# Shield_Kazi.net
KiCad netlist of a schematic drawn in EAGLE
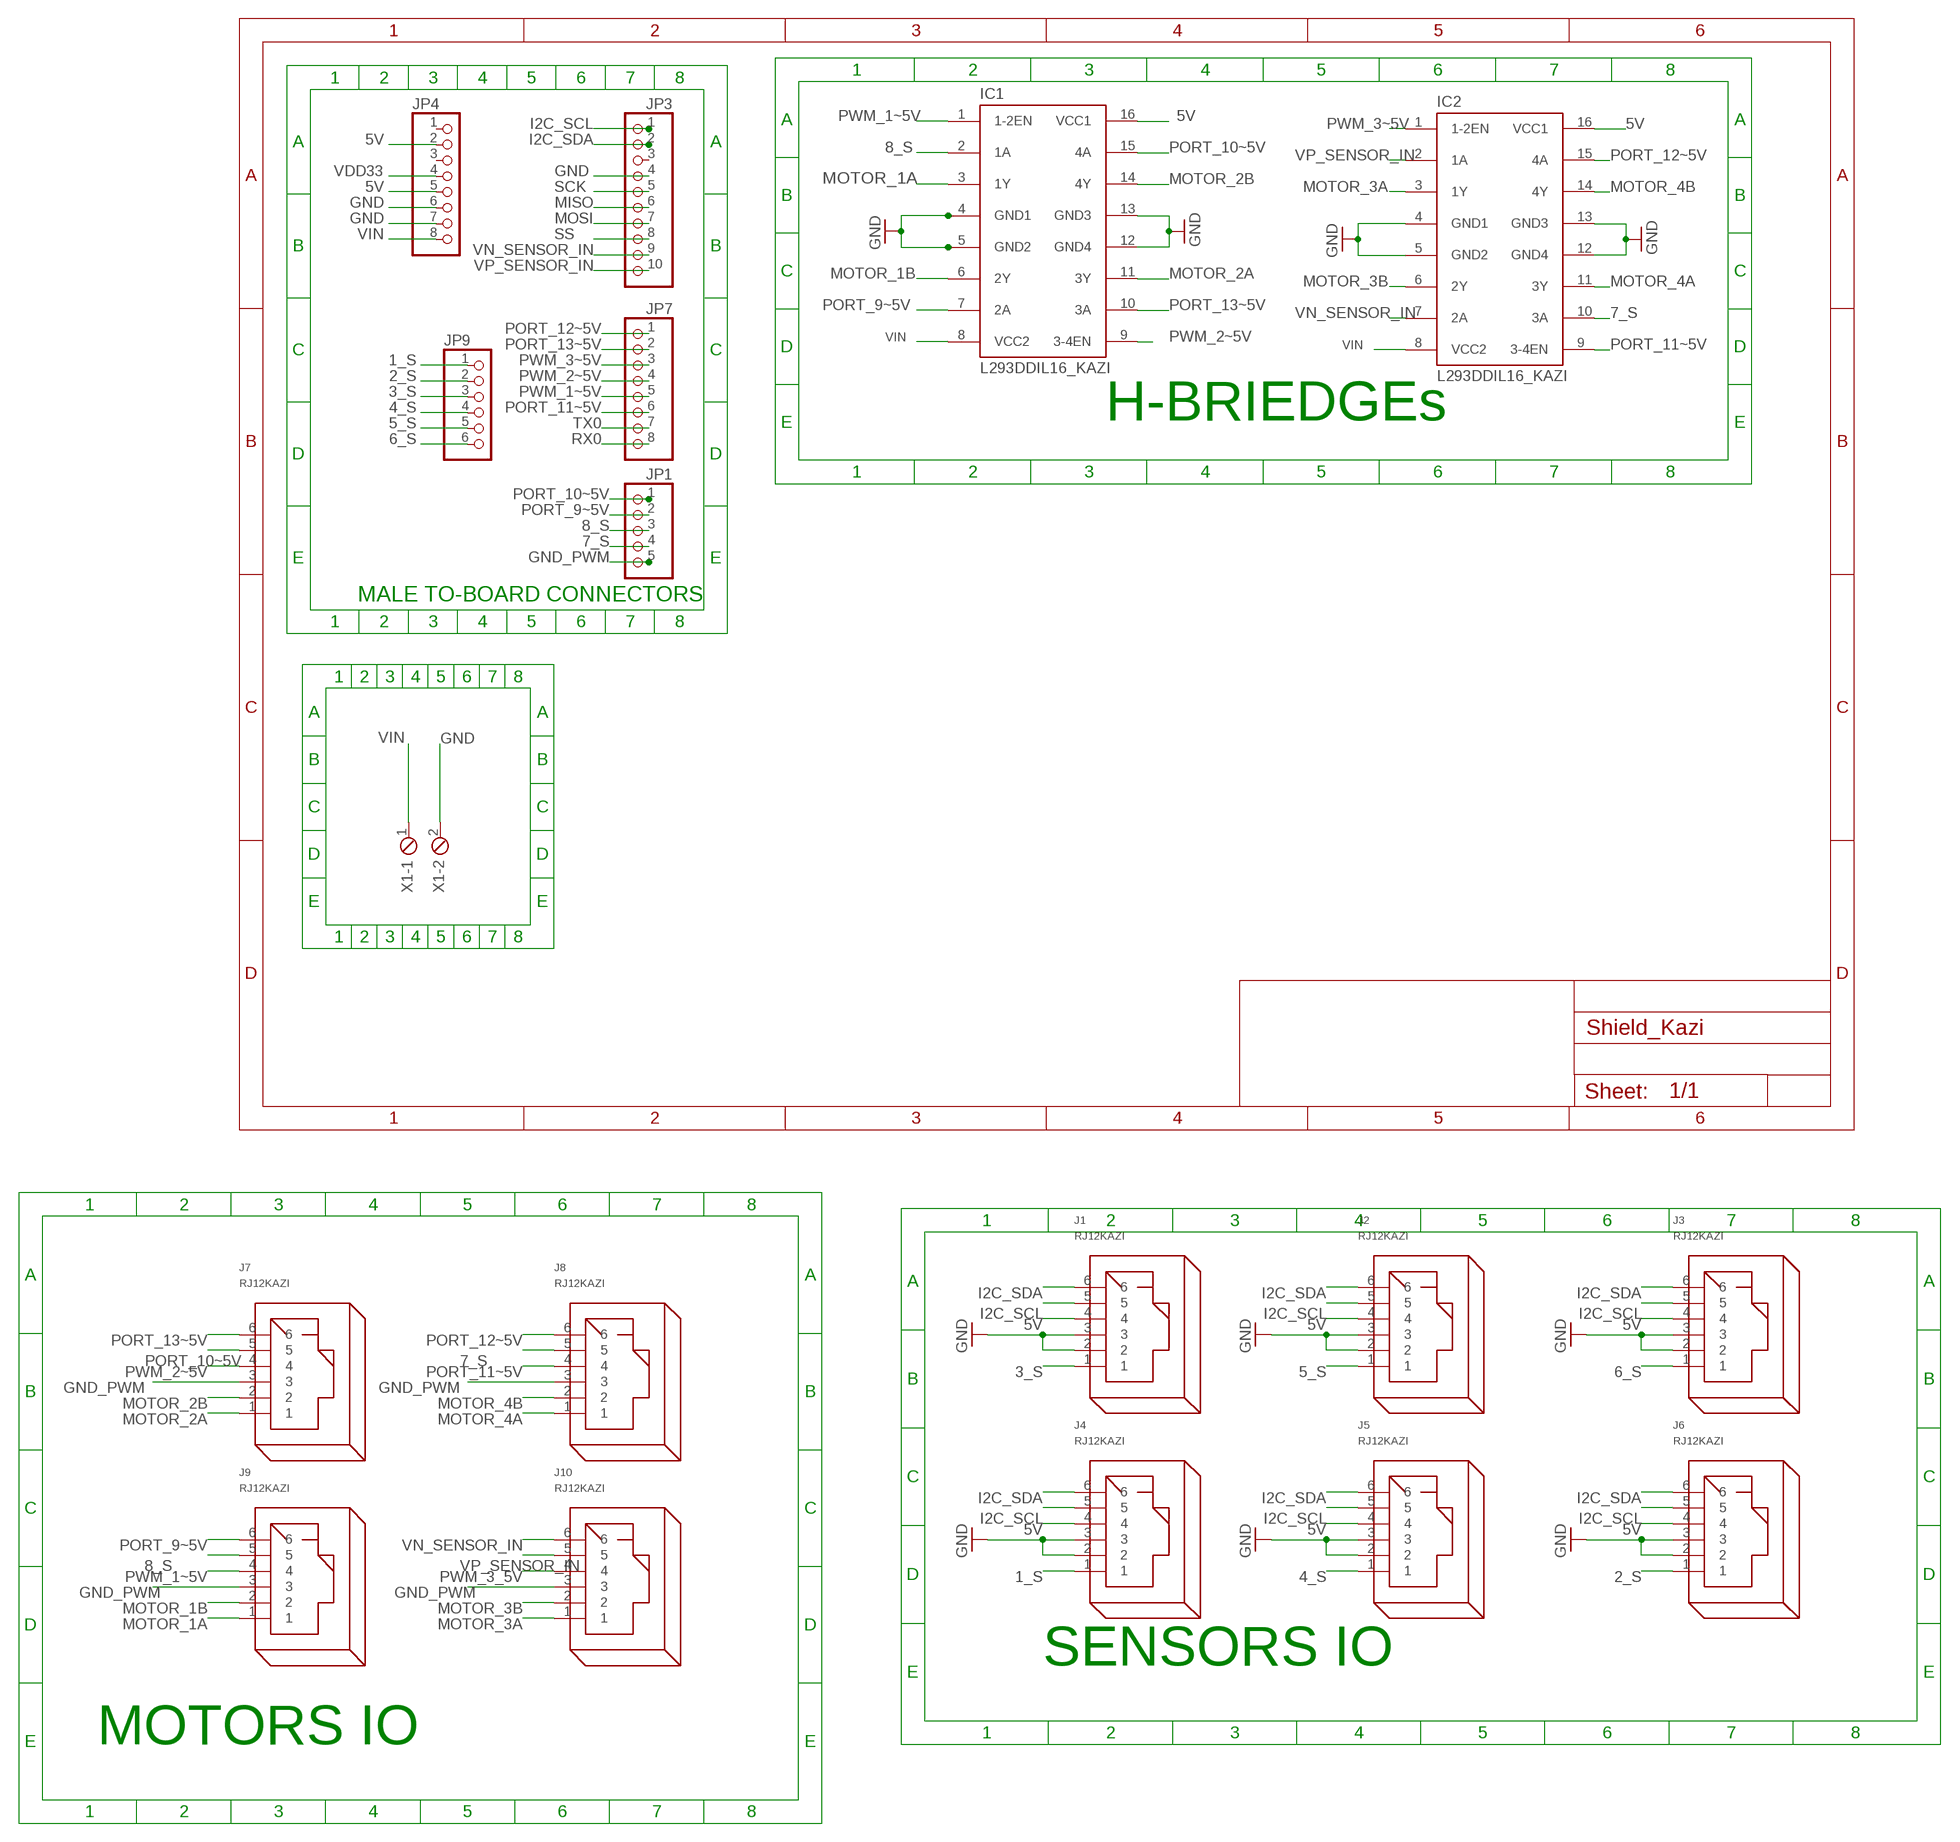
[diagram p0: schematic, sheet 1]

(export (version "E")
  (design (tool "Eeschema 10.0.6"))
  (components
    (comp (ref "IC1")
      (value "L293DDIL16_KAZI")
      (footprint "eagle-import:DIL16_KAZI")
      (libsource (lib "eagle-import") (part "L293DDIL16_KAZI"))
    )
    (comp (ref "IC2")
      (value "L293DDIL16_KAZI")
      (footprint "eagle-import:DIL16_KAZI")
      (libsource (lib "eagle-import") (part "L293DDIL16_KAZI"))
    )
    (comp (ref "J1")
      (value "RJ12KAZI")
      (footprint "eagle-import:RJ12_KAZI")
      (libsource (lib "eagle-import") (part "RJ12KAZI"))
    )
    (comp (ref "J2")
      (value "RJ12KAZI")
      (footprint "eagle-import:RJ12_KAZI")
      (libsource (lib "eagle-import") (part "RJ12KAZI"))
    )
    (comp (ref "J3")
      (value "RJ12KAZI")
      (footprint "eagle-import:RJ12_KAZI")
      (libsource (lib "eagle-import") (part "RJ12KAZI"))
    )
    (comp (ref "J4")
      (value "RJ12KAZI")
      (footprint "eagle-import:RJ12_KAZI")
      (libsource (lib "eagle-import") (part "RJ12KAZI"))
    )
    (comp (ref "J5")
      (value "RJ12KAZI")
      (footprint "eagle-import:RJ12_KAZI")
      (libsource (lib "eagle-import") (part "RJ12KAZI"))
    )
    (comp (ref "J6")
      (value "RJ12KAZI")
      (footprint "eagle-import:RJ12_KAZI")
      (libsource (lib "eagle-import") (part "RJ12KAZI"))
    )
    (comp (ref "J7")
      (value "RJ12KAZI")
      (footprint "eagle-import:RJ12_KAZI")
      (libsource (lib "eagle-import") (part "RJ12KAZI"))
    )
    (comp (ref "J8")
      (value "RJ12KAZI")
      (footprint "eagle-import:RJ12_KAZI")
      (libsource (lib "eagle-import") (part "RJ12KAZI"))
    )
    (comp (ref "J9")
      (value "RJ12KAZI")
      (footprint "eagle-import:RJ12_KAZI")
      (libsource (lib "eagle-import") (part "RJ12KAZI"))
    )
    (comp (ref "J10")
      (value "RJ12KAZI")
      (footprint "eagle-import:RJ12_KAZI")
      (libsource (lib "eagle-import") (part "RJ12KAZI"))
    )
    (comp (ref "JP1")
      (value "PINHD-1X5_2.54-SMD")
      (footprint "eagle-import:1X05SMD")
      (libsource (lib "eagle-import") (part "PINHD-1X5_2.54-SMD"))
    )
    (comp (ref "JP3")
      (value "PINHD-1X10_2.54-SMD")
      (footprint "eagle-import:1X10SMD")
      (libsource (lib "eagle-import") (part "PINHD-1X10_2.54-SMD"))
    )
    (comp (ref "JP4")
      (value "PINHD-1X8_2.54-SMD")
      (footprint "eagle-import:1X08SMD")
      (libsource (lib "eagle-import") (part "PINHD-1X8_2.54-SMD"))
    )
    (comp (ref "JP7")
      (value "PINHD-1X8_2.54-SMD")
      (footprint "eagle-import:1X08SMD")
      (libsource (lib "eagle-import") (part "PINHD-1X8_2.54-SMD"))
    )
    (comp (ref "JP9")
      (value "PINHD-1X6_2.54-SMD")
      (footprint "eagle-import:1X06SMD")
      (libsource (lib "eagle-import") (part "PINHD-1X6_2.54-SMD"))
    )
    (comp (ref "X1")
      (value "MPT21.3")
      (footprint "eagle-import:2POL254_1.3")
      (libsource (lib "eagle-import") (part "MPT21.3"))
    )
  )
  (nets
    (net (code "1") (name "/1_S") (class "Default")
      (node (ref "J4") (pin "1") (pinfunction "1_1") (pintype "bidirectional"))
      (node (ref "JP9") (pin "1") (pinfunction "1_1") (pintype "passive"))
    )
    (net (code "2") (name "/2_S") (class "Default")
      (node (ref "J6") (pin "1") (pinfunction "1_1") (pintype "bidirectional"))
      (node (ref "JP9") (pin "2") (pinfunction "2_2") (pintype "passive"))
    )
    (net (code "3") (name "/3_S") (class "Default")
      (node (ref "J1") (pin "1") (pinfunction "1_1") (pintype "bidirectional"))
      (node (ref "JP9") (pin "3") (pinfunction "3_3") (pintype "passive"))
    )
    (net (code "4") (name "/4_S") (class "Default")
      (node (ref "J5") (pin "1") (pinfunction "1_1") (pintype "bidirectional"))
      (node (ref "JP9") (pin "4") (pinfunction "4_4") (pintype "passive"))
    )
    (net (code "5") (name "/5V") (class "Default")
      (node (ref "IC1") (pin "16") (pinfunction "VCC1_16") (pintype "power_in"))
      (node (ref "IC2") (pin "16") (pinfunction "VCC1_16") (pintype "power_in"))
      (node (ref "J1") (pin "4") (pinfunction "4_4") (pintype "bidirectional"))
      (node (ref "J2") (pin "4") (pinfunction "4_4") (pintype "bidirectional"))
      (node (ref "J3") (pin "4") (pinfunction "4_4") (pintype "bidirectional"))
      (node (ref "J4") (pin "4") (pinfunction "4_4") (pintype "bidirectional"))
      (node (ref "J5") (pin "4") (pinfunction "4_4") (pintype "bidirectional"))
      (node (ref "J6") (pin "4") (pinfunction "4_4") (pintype "bidirectional"))
      (node (ref "JP4") (pin "2") (pinfunction "2_2") (pintype "passive"))
      (node (ref "JP4") (pin "5") (pinfunction "5_5") (pintype "passive"))
    )
    (net (code "6") (name "/5_S") (class "Default")
      (node (ref "J2") (pin "1") (pinfunction "1_1") (pintype "bidirectional"))
      (node (ref "JP9") (pin "5") (pinfunction "5_5") (pintype "passive"))
    )
    (net (code "7") (name "/6_S") (class "Default")
      (node (ref "J3") (pin "1") (pinfunction "1_1") (pintype "bidirectional"))
      (node (ref "JP9") (pin "6") (pinfunction "6_6") (pintype "passive"))
    )
    (net (code "8") (name "/7_S") (class "Default")
      (node (ref "IC2") (pin "10") (pinfunction "3A_10") (pintype "input"))
      (node (ref "J8") (pin "5") (pinfunction "5_5") (pintype "bidirectional"))
      (node (ref "JP1") (pin "4") (pinfunction "4_4") (pintype "passive"))
    )
    (net (code "9") (name "/8_S") (class "Default")
      (node (ref "IC1") (pin "2") (pinfunction "1A_2") (pintype "input"))
      (node (ref "J9") (pin "5") (pinfunction "5_5") (pintype "bidirectional"))
      (node (ref "JP1") (pin "3") (pinfunction "3_3") (pintype "passive"))
    )
    (net (code "10") (name "/GND_PWM") (class "Default")
      (node (ref "J10") (pin "3") (pinfunction "3_3") (pintype "bidirectional"))
      (node (ref "J7") (pin "3") (pinfunction "3_3") (pintype "bidirectional"))
      (node (ref "J8") (pin "3") (pinfunction "3_3") (pintype "bidirectional"))
      (node (ref "J9") (pin "3") (pinfunction "3_3") (pintype "bidirectional"))
      (node (ref "JP1") (pin "5") (pinfunction "5_5") (pintype "passive"))
    )
    (net (code "11") (name "/I2C_SCL") (class "Default")
      (node (ref "J1") (pin "5") (pinfunction "5_5") (pintype "bidirectional"))
      (node (ref "J2") (pin "5") (pinfunction "5_5") (pintype "bidirectional"))
      (node (ref "J3") (pin "5") (pinfunction "5_5") (pintype "bidirectional"))
      (node (ref "J4") (pin "5") (pinfunction "5_5") (pintype "bidirectional"))
      (node (ref "J5") (pin "5") (pinfunction "5_5") (pintype "bidirectional"))
      (node (ref "J6") (pin "5") (pinfunction "5_5") (pintype "bidirectional"))
      (node (ref "JP3") (pin "1") (pinfunction "1_1") (pintype "passive"))
    )
    (net (code "12") (name "/I2C_SDA") (class "Default")
      (node (ref "J1") (pin "6") (pinfunction "6_6") (pintype "bidirectional"))
      (node (ref "J2") (pin "6") (pinfunction "6_6") (pintype "bidirectional"))
      (node (ref "J3") (pin "6") (pinfunction "6_6") (pintype "bidirectional"))
      (node (ref "J4") (pin "6") (pinfunction "6_6") (pintype "bidirectional"))
      (node (ref "J5") (pin "6") (pinfunction "6_6") (pintype "bidirectional"))
      (node (ref "J6") (pin "6") (pinfunction "6_6") (pintype "bidirectional"))
      (node (ref "JP3") (pin "2") (pinfunction "2_2") (pintype "passive"))
    )
    (net (code "13") (name "/MISO") (class "Default")
      (node (ref "JP3") (pin "6") (pinfunction "6_6") (pintype "passive"))
    )
    (net (code "14") (name "/MOSI") (class "Default")
      (node (ref "JP3") (pin "7") (pinfunction "7_7") (pintype "passive"))
    )
    (net (code "15") (name "/MOTOR_1A") (class "Default")
      (node (ref "IC1") (pin "3") (pinfunction "1Y_3") (pintype "output"))
      (node (ref "J9") (pin "1") (pinfunction "1_1") (pintype "bidirectional"))
    )
    (net (code "16") (name "/MOTOR_1B") (class "Default")
      (node (ref "IC1") (pin "6") (pinfunction "2Y_6") (pintype "output"))
      (node (ref "J9") (pin "2") (pinfunction "2_2") (pintype "bidirectional"))
    )
    (net (code "17") (name "/MOTOR_2A") (class "Default")
      (node (ref "IC1") (pin "11") (pinfunction "3Y_11") (pintype "output"))
      (node (ref "J7") (pin "1") (pinfunction "1_1") (pintype "bidirectional"))
    )
    (net (code "18") (name "/MOTOR_2B") (class "Default")
      (node (ref "IC1") (pin "14") (pinfunction "4Y_14") (pintype "output"))
      (node (ref "J7") (pin "2") (pinfunction "2_2") (pintype "bidirectional"))
    )
    (net (code "19") (name "/MOTOR_3A") (class "Default")
      (node (ref "IC2") (pin "3") (pinfunction "1Y_3") (pintype "output"))
      (node (ref "J10") (pin "1") (pinfunction "1_1") (pintype "bidirectional"))
    )
    (net (code "20") (name "/MOTOR_3B") (class "Default")
      (node (ref "IC2") (pin "6") (pinfunction "2Y_6") (pintype "output"))
      (node (ref "J10") (pin "2") (pinfunction "2_2") (pintype "bidirectional"))
    )
    (net (code "21") (name "/MOTOR_4A") (class "Default")
      (node (ref "IC2") (pin "11") (pinfunction "3Y_11") (pintype "output"))
      (node (ref "J8") (pin "1") (pinfunction "1_1") (pintype "bidirectional"))
    )
    (net (code "22") (name "/MOTOR_4B") (class "Default")
      (node (ref "IC2") (pin "14") (pinfunction "4Y_14") (pintype "output"))
      (node (ref "J8") (pin "2") (pinfunction "2_2") (pintype "bidirectional"))
    )
    (net (code "23") (name "/PORT_9~{5V}") (class "Default")
      (node (ref "IC1") (pin "7") (pinfunction "2A_7") (pintype "input"))
      (node (ref "J9") (pin "6") (pinfunction "6_6") (pintype "bidirectional"))
      (node (ref "JP1") (pin "2") (pinfunction "2_2") (pintype "passive"))
    )
    (net (code "24") (name "/PORT_10~{5V}") (class "Default")
      (node (ref "IC1") (pin "15") (pinfunction "4A_15") (pintype "input"))
      (node (ref "J7") (pin "5") (pinfunction "5_5") (pintype "bidirectional"))
      (node (ref "JP1") (pin "1") (pinfunction "1_1") (pintype "passive"))
    )
    (net (code "25") (name "/PORT_11~{5V}") (class "Default")
      (node (ref "IC2") (pin "9") (pinfunction "3-4EN_9") (pintype "input"))
      (node (ref "J8") (pin "4") (pinfunction "4_4") (pintype "bidirectional"))
      (node (ref "JP7") (pin "6") (pinfunction "6_6") (pintype "passive"))
    )
    (net (code "26") (name "/PORT_12~{5V}") (class "Default")
      (node (ref "IC2") (pin "15") (pinfunction "4A_15") (pintype "input"))
      (node (ref "J8") (pin "6") (pinfunction "6_6") (pintype "bidirectional"))
      (node (ref "JP7") (pin "1") (pinfunction "1_1") (pintype "passive"))
    )
    (net (code "27") (name "/PORT_13~{5V}") (class "Default")
      (node (ref "IC1") (pin "10") (pinfunction "3A_10") (pintype "input"))
      (node (ref "J7") (pin "6") (pinfunction "6_6") (pintype "bidirectional"))
      (node (ref "JP7") (pin "2") (pinfunction "2_2") (pintype "passive"))
    )
    (net (code "28") (name "/PWM_1~{5V}") (class "Default")
      (node (ref "IC1") (pin "1") (pinfunction "1-2EN_1") (pintype "input"))
      (node (ref "J9") (pin "4") (pinfunction "4_4") (pintype "bidirectional"))
      (node (ref "JP7") (pin "5") (pinfunction "5_5") (pintype "passive"))
    )
    (net (code "29") (name "/PWM_2~{5V}") (class "Default")
      (node (ref "IC1") (pin "9") (pinfunction "3-4EN_9") (pintype "input"))
      (node (ref "J7") (pin "4") (pinfunction "4_4") (pintype "bidirectional"))
      (node (ref "JP7") (pin "4") (pinfunction "4_4") (pintype "passive"))
    )
    (net (code "30") (name "/PWM_3_5V") (class "Default")
      (node (ref "J10") (pin "4") (pinfunction "4_4") (pintype "bidirectional"))
    )
    (net (code "31") (name "/PWM_3~{5V}") (class "Default")
      (node (ref "IC2") (pin "1") (pinfunction "1-2EN_1") (pintype "input"))
      (node (ref "JP7") (pin "3") (pinfunction "3_3") (pintype "passive"))
    )
    (net (code "32") (name "/RX0") (class "Default")
      (node (ref "JP7") (pin "8") (pinfunction "8_8") (pintype "passive"))
    )
    (net (code "33") (name "/SCK") (class "Default")
      (node (ref "JP3") (pin "5") (pinfunction "5_5") (pintype "passive"))
    )
    (net (code "34") (name "/SS") (class "Default")
      (node (ref "JP3") (pin "8") (pinfunction "8_8") (pintype "passive"))
    )
    (net (code "35") (name "/TX0") (class "Default")
      (node (ref "JP7") (pin "7") (pinfunction "7_7") (pintype "passive"))
    )
    (net (code "36") (name "/VDD33") (class "Default")
      (node (ref "JP4") (pin "4") (pinfunction "4_4") (pintype "passive"))
    )
    (net (code "37") (name "/VIN") (class "Default")
      (node (ref "IC1") (pin "8") (pinfunction "VCC2_8") (pintype "power_in"))
      (node (ref "IC2") (pin "8") (pinfunction "VCC2_8") (pintype "power_in"))
      (node (ref "JP4") (pin "8") (pinfunction "8_8") (pintype "passive"))
      (node (ref "X1") (pin "1") (pinfunction "1_1") (pintype "passive"))
    )
    (net (code "38") (name "/VN_SENSOR_IN") (class "Default")
      (node (ref "IC2") (pin "7") (pinfunction "2A_7") (pintype "input"))
      (node (ref "J10") (pin "6") (pinfunction "6_6") (pintype "bidirectional"))
      (node (ref "JP3") (pin "9") (pinfunction "9_9") (pintype "passive"))
    )
    (net (code "39") (name "/VP_SENSOR_IN") (class "Default")
      (node (ref "IC2") (pin "2") (pinfunction "1A_2") (pintype "input"))
      (node (ref "J10") (pin "5") (pinfunction "5_5") (pintype "bidirectional"))
      (node (ref "JP3") (pin "10") (pinfunction "10_10") (pintype "passive"))
    )
    (net (code "40") (name "GND") (class "Default")
      (node (ref "IC1") (pin "12") (pinfunction "GND4_12") (pintype "power_in"))
      (node (ref "IC1") (pin "13") (pinfunction "GND3_13") (pintype "power_in"))
      (node (ref "IC1") (pin "4") (pinfunction "GND1_4") (pintype "power_in"))
      (node (ref "IC1") (pin "5") (pinfunction "GND2_5") (pintype "power_in"))
      (node (ref "IC2") (pin "12") (pinfunction "GND4_12") (pintype "power_in"))
      (node (ref "IC2") (pin "13") (pinfunction "GND3_13") (pintype "power_in"))
      (node (ref "IC2") (pin "4") (pinfunction "GND1_4") (pintype "power_in"))
      (node (ref "IC2") (pin "5") (pinfunction "GND2_5") (pintype "power_in"))
      (node (ref "J1") (pin "2") (pinfunction "2_2") (pintype "bidirectional"))
      (node (ref "J1") (pin "3") (pinfunction "3_3") (pintype "bidirectional"))
      (node (ref "J2") (pin "2") (pinfunction "2_2") (pintype "bidirectional"))
      (node (ref "J2") (pin "3") (pinfunction "3_3") (pintype "bidirectional"))
      (node (ref "J3") (pin "2") (pinfunction "2_2") (pintype "bidirectional"))
      (node (ref "J3") (pin "3") (pinfunction "3_3") (pintype "bidirectional"))
      (node (ref "J4") (pin "2") (pinfunction "2_2") (pintype "bidirectional"))
      (node (ref "J4") (pin "3") (pinfunction "3_3") (pintype "bidirectional"))
      (node (ref "J5") (pin "2") (pinfunction "2_2") (pintype "bidirectional"))
      (node (ref "J5") (pin "3") (pinfunction "3_3") (pintype "bidirectional"))
      (node (ref "J6") (pin "2") (pinfunction "2_2") (pintype "bidirectional"))
      (node (ref "J6") (pin "3") (pinfunction "3_3") (pintype "bidirectional"))
      (node (ref "JP3") (pin "4") (pinfunction "4_4") (pintype "passive"))
      (node (ref "JP4") (pin "6") (pinfunction "6_6") (pintype "passive"))
      (node (ref "JP4") (pin "7") (pinfunction "7_7") (pintype "passive"))
      (node (ref "X1") (pin "2") (pinfunction "1_2") (pintype "passive"))
    )
    (net (code "41") (name "unconnected-(JP3-Pad3)") (class "Default")
      (node (ref "JP3") (pin "3") (pinfunction "3_3") (pintype "passive"))
    )
    (net (code "42") (name "unconnected-(JP4-Pad1)") (class "Default")
      (node (ref "JP4") (pin "1") (pinfunction "1_1") (pintype "passive"))
    )
    (net (code "43") (name "unconnected-(JP4-Pad3)") (class "Default")
      (node (ref "JP4") (pin "3") (pinfunction "3_3") (pintype "passive"))
    )
  )
)
